# MCU.net
KiCad netlist of a schematic drawn in Altium Designer
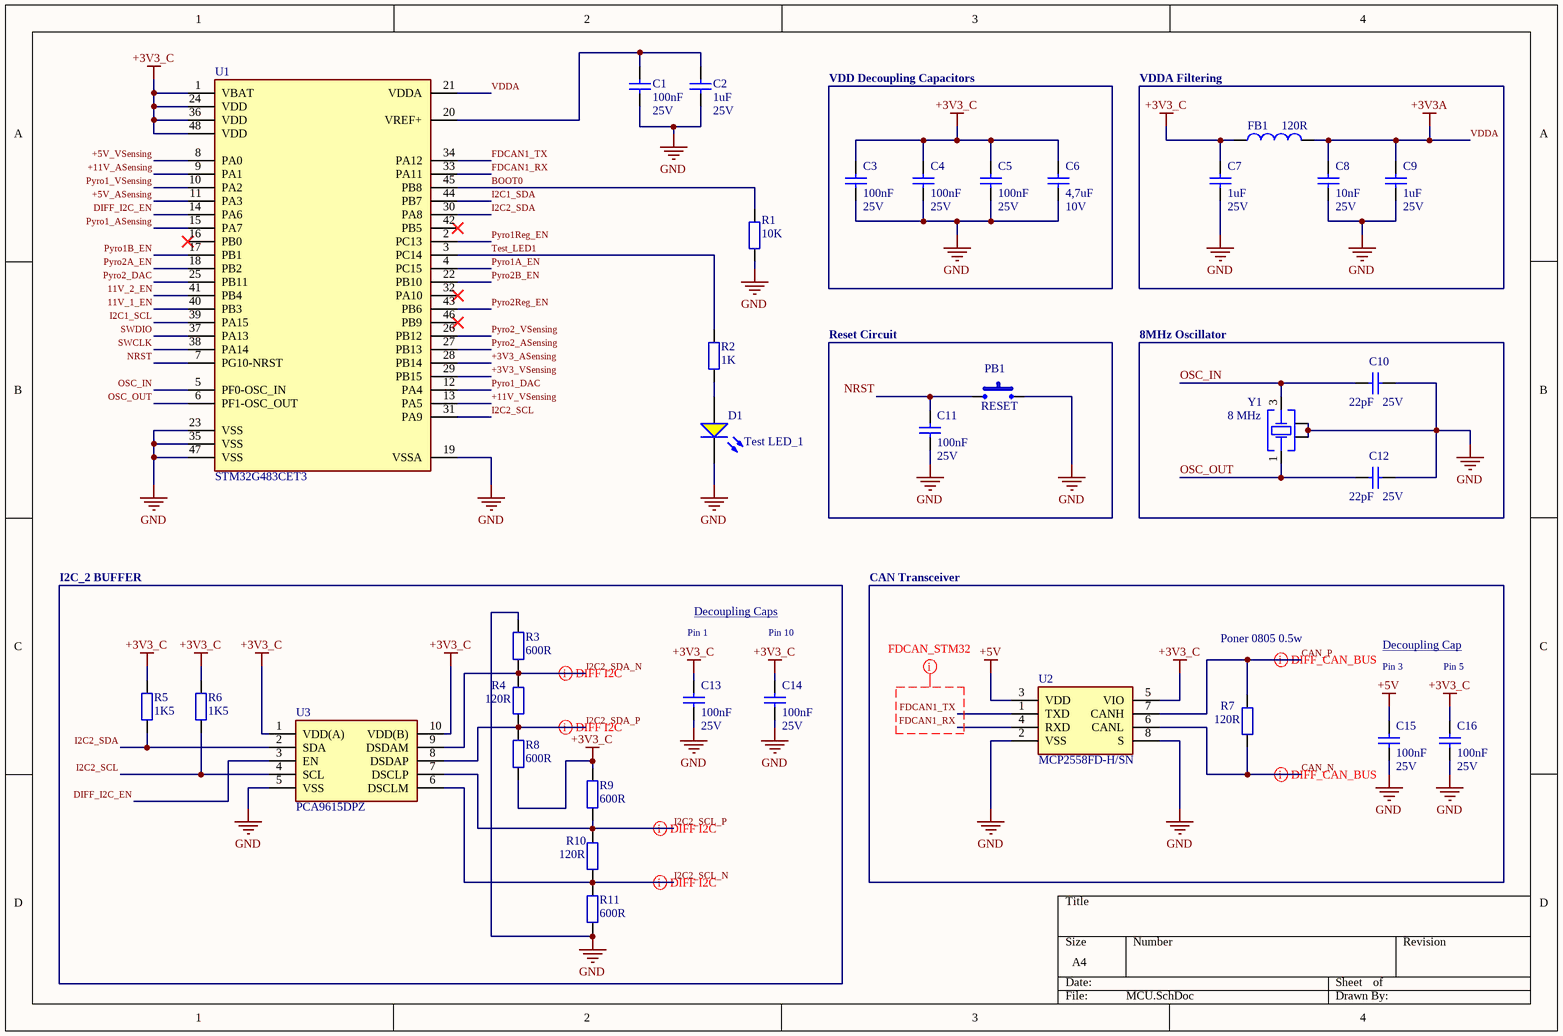
[diagram p0: MCU.SchDoc]

(export (version "E")
  (design (tool "Eeschema 10.0.6"))
  (components
    (comp (ref "C1")
      (value "100nF")
      (footprint "MY_0603")
      (description "Capacitor, 100nF, 0603, 25V")
      (fields
        (field (name "VOLTAGE") "25V")
        (field (name "MANUFACTURER") "Wurth Elektronik")
        (field (name "MANUFACTURER PART NUMBER") "885012206071")
      )
      (libsource (lib "LEEM UPM") (part "Cap ceramic"))
    )
    (comp (ref "C2")
      (value "1uF")
      (footprint "MY_0603")
      (description "Capacitor, 1uF, 0603, 25V")
      (fields
        (field (name "VOLTE") "25V")
        (field (name "MANUFACTURER") "Wurth Elektronik")
        (field (name "MANUFACTURER PART NUMBER") "885012206052")
      )
      (libsource (lib "LEEM UPM") (part "Cap ceramic"))
    )
    (comp (ref "C3")
      (value "100nF")
      (footprint "MY_0603")
      (description "Capacitor, 100nF, 0603, 25V")
      (fields
        (field (name "VOLTAGE") "25V")
        (field (name "MANUFACTURER") "Wurth Elektronik")
        (field (name "MANUFACTURER PART NUMBER") "885012206071")
      )
      (libsource (lib "LEEM UPM") (part "Cap ceramic"))
    )
    (comp (ref "C4")
      (value "100nF")
      (footprint "MY_0603")
      (description "Capacitor, 100nF, 0603, 25V")
      (fields
        (field (name "VOLTAGE") "25V")
        (field (name "MANUFACTURER") "Wurth Elektronik")
        (field (name "MANUFACTURER PART NUMBER") "885012206071")
      )
      (libsource (lib "LEEM UPM") (part "Cap ceramic"))
    )
    (comp (ref "C5")
      (value "100nF")
      (footprint "MY_0603")
      (description "Capacitor, 100nF, 0603, 25V")
      (fields
        (field (name "VOLTAGE") "25V")
        (field (name "MANUFACTURER") "Wurth Elektronik")
        (field (name "MANUFACTURER PART NUMBER") "885012206071")
      )
      (libsource (lib "LEEM UPM") (part "Cap ceramic"))
    )
    (comp (ref "C6")
      (value "4,7uF")
      (footprint "MY_0603")
      (description "Capacitor, 4.7uF, 0603, 25V")
      (fields
        (field (name "VOLTE") "10V")
        (field (name "MANUFACTURER") "Wurth Elektronik")
        (field (name "MANUFACTURER PART NUMBER") "885012106012")
      )
      (libsource (lib "LEEM UPM") (part "Cap ceramic"))
    )
    (comp (ref "C7")
      (value "1uF")
      (footprint "MY_0603")
      (description "Capacitor, 1uF, 0603, 25V")
      (fields
        (field (name "VOLTE") "25V")
        (field (name "MANUFACTURER") "Wurth Elektronik")
        (field (name "MANUFACTURER PART NUMBER") "885012206052")
      )
      (libsource (lib "LEEM UPM") (part "Cap ceramic"))
    )
    (comp (ref "C8")
      (value "25V")
      (footprint "MY_0603")
      (description "Capacitor, 10nF, 0603, 25V")
      (fields
        (field (name "ALTIUM_VALUE") "10nF")
        (field (name "MANUFACTURER") "Wurth Elektronik")
        (field (name "MANUFACTURER PART NUMBER") "885012206065")
      )
      (libsource (lib "LEEM UPM") (part "Cap ceramic"))
    )
    (comp (ref "C9")
      (value "1uF")
      (footprint "MY_0603")
      (description "Capacitor, 1uF, 0603, 25V")
      (fields
        (field (name "VOLTE") "25V")
        (field (name "MANUFACTURER") "Wurth Elektronik")
        (field (name "MANUFACTURER PART NUMBER") "885012206052")
      )
      (libsource (lib "LEEM UPM") (part "Cap ceramic"))
    )
    (comp (ref "C10")
      (value "22pF")
      (footprint "MY_0603")
      (description "Capacitor, 22pF, 0603, 25V")
      (fields
        (field (name "VOLTE") "25V")
        (field (name "MANUFACTURER") "Wurth Elektronik")
        (field (name "MANUFACTURER PART NUMBER") "885012006034")
      )
      (libsource (lib "LEEM UPM") (part "Cap ceramic"))
    )
    (comp (ref "C11")
      (value "100nF")
      (footprint "MY_0603")
      (description "Capacitor, 100nF, 0603, 25V")
      (fields
        (field (name "VOLTAGE") "25V")
        (field (name "MANUFACTURER") "Wurth Elektronik")
        (field (name "MANUFACTURER PART NUMBER") "885012206071")
      )
      (libsource (lib "LEEM UPM") (part "Cap ceramic"))
    )
    (comp (ref "C12")
      (value "22pF")
      (footprint "MY_0603")
      (description "Capacitor, 22pF, 0603, 25V")
      (fields
        (field (name "VOLTE") "25V")
        (field (name "MANUFACTURER") "Wurth Elektronik")
        (field (name "MANUFACTURER PART NUMBER") "885012006034")
      )
      (libsource (lib "LEEM UPM") (part "Cap ceramic"))
    )
    (comp (ref "C13")
      (value "100nF")
      (footprint "MY_0603")
      (description "Capacitor, 100nF, 0603, 25V")
      (fields
        (field (name "VOLTAGE") "25V")
        (field (name "MANUFACTURER") "Wurth Elektronik")
        (field (name "MANUFACTURER PART NUMBER") "885012206071")
      )
      (libsource (lib "LEEM UPM") (part "Cap ceramic"))
    )
    (comp (ref "C14")
      (value "100nF")
      (footprint "MY_0603")
      (description "Capacitor, 100nF, 0603, 25V")
      (fields
        (field (name "VOLTAGE") "25V")
        (field (name "MANUFACTURER") "Wurth Elektronik")
        (field (name "MANUFACTURER PART NUMBER") "885012206071")
      )
      (libsource (lib "LEEM UPM") (part "Cap ceramic"))
    )
    (comp (ref "C15")
      (value "100nF")
      (footprint "MY_0603")
      (description "Capacitor, 100nF, 0603, 25V")
      (fields
        (field (name "VOLTAGE") "25V")
        (field (name "MANUFACTURER") "Wurth Elektronik")
        (field (name "MANUFACTURER PART NUMBER") "885012206071")
      )
      (libsource (lib "LEEM UPM") (part "Cap ceramic"))
    )
    (comp (ref "C16")
      (value "100nF")
      (footprint "MY_0603")
      (description "Capacitor, 100nF, 0603, 25V")
      (fields
        (field (name "VOLTAGE") "25V")
        (field (name "MANUFACTURER") "Wurth Elektronik")
        (field (name "MANUFACTURER PART NUMBER") "885012206071")
      )
      (libsource (lib "LEEM UPM") (part "Cap ceramic"))
    )
    (comp (ref "D1")
      (value "Test LED_1")
      (footprint "WL-SMCW_0805_150080xx75000")
      (description "LED, 0805, Yellow")
      (fields
        (field (name "MANUFACTURER") "Wurth Elektronik")
        (field (name "MANUFACTURER PART NUMBER") "150080YS75000")
      )
      (libsource (lib "Altium Content Vault") (part "LED_Yellow_2A-1K"))
    )
    (comp (ref "FB1")
      (value "120R")
      (footprint "WE-CBF_0603_L1.6W0.8H0.8_HC")
      (description "Ferrite Bead, 120R at 100MHz, 0603, 2 A")
      (fields
        (field (name "MANUFACTURER") "Wurth Elektronik")
        (field (name "MANUFACTURER PART NUMBER") "742792625")
      )
      (libsource (lib "Altium Content Vault") (part "Ferrite"))
    )
    (comp (ref "PB1")
      (value "RESET")
      (footprint "Push Button-Footprint-1")
      (description "Push Button")
      (fields (field (name "SOURCE") "IFS_Altium.SchLib"))
      (libsource (lib "LEEM UPM") (part "Push Button"))
    )
    (comp (ref "R1")
      (value "10K")
      (footprint "R0603-0.45")
      (description "Resistor, 10K, 0603, 0.1W")
      (fields (field (name "MANUFACTURER") "Wurth") (field (name "MANUFACTURER PART NUMBER") "560112116005"))
      (libsource (lib "IFS_Altium") (part "R"))
    )
    (comp (ref "R2")
      (value "1K")
      (footprint "R0603-0.45")
      (description "Resistor, 1K, 0603, 0.1W")
      (fields (field (name "MANUFACTURER") "Wurth") (field (name "MANUFACTURER PART NUMBER") "560112116014"))
      (libsource (lib "LEEM UPM") (part "RK73H2ALTD1004F"))
    )
    (comp (ref "R3")
      (value "600R")
      (footprint "R0805-0.45")
      (description "Resistor, 600R, 0805, 0.5W")
      (fields
        (field (name "MANUFACTURER") "Panasonic")
        (field (name "MANUFACTURER PART NUMBER") "ERJ-6ENF6040V")
      )
      (libsource (lib "LEEM UPM") (part "RK73H2ALTD1004F"))
    )
    (comp (ref "R4")
      (value "120R")
      (footprint "R0805-0.45")
      (description "Resistor, 120R, 0805, 0.25W")
      (fields
        (field (name "MANUFACTURER") "Vishay")
        (field (name "MANUFACTURER PART NUMBER") "RCS0805120RFKEA")
      )
      (libsource (lib "LEEM UPM") (part "RK73H2ALTD1004F"))
    )
    (comp (ref "R5")
      (value "1K5")
      (footprint "R0603-0.45")
      (description "Resistor, 1.5K, 0603, 0.1W")
      (fields (field (name "MANUFACTURER") "Wurth") (field (name "MANUFACTURER PART NUMBER") "560112116038"))
      (libsource (lib "LEEM UPM") (part "RK73H2ALTD1004F"))
    )
    (comp (ref "R6")
      (value "1K5")
      (footprint "R0603-0.45")
      (description "Resistor, 1.5K, 0603, 0.1W")
      (fields (field (name "MANUFACTURER") "Wurth") (field (name "MANUFACTURER PART NUMBER") "560112116038"))
      (libsource (lib "LEEM UPM") (part "RK73H2ALTD1004F"))
    )
    (comp (ref "R7")
      (value "120R")
      (footprint "R0805-0.45")
      (description "Resistor, 120R, 0805, 0.25W")
      (fields
        (field (name "MANUFACTURER") "Vishay")
        (field (name "MANUFACTURER PART NUMBER") "RCS0805120RFKEA")
      )
      (libsource (lib "LEEM UPM") (part "RK73H2ALTD1004F"))
    )
    (comp (ref "R8")
      (value "600R")
      (footprint "R0805-0.45")
      (description "Resistor, 600R, 0805, 0.5W")
      (fields
        (field (name "MANUFACTURER") "Panasonic")
        (field (name "MANUFACTURER PART NUMBER") "ERJ-6ENF6040V")
      )
      (libsource (lib "LEEM UPM") (part "RK73H2ALTD1004F"))
    )
    (comp (ref "R9")
      (value "600R")
      (footprint "R0805-0.45")
      (description "Resistor, 600R, 0805, 0.5W")
      (fields
        (field (name "MANUFACTURER") "Panasonic")
        (field (name "MANUFACTURER PART NUMBER") "ERJ-6ENF6040V")
      )
      (libsource (lib "LEEM UPM") (part "RK73H2ALTD1004F"))
    )
    (comp (ref "R10")
      (value "120R")
      (footprint "R0805-0.45")
      (description "Resistor, 120R, 0805, 0.25W")
      (fields
        (field (name "MANUFACTURER") "Vishay")
        (field (name "MANUFACTURER PART NUMBER") "RCS0805120RFKEA")
      )
      (libsource (lib "LEEM UPM") (part "RK73H2ALTD1004F"))
    )
    (comp (ref "R11")
      (value "600R")
      (footprint "R0805-0.45")
      (description "Resistor, 600R, 0805, 0.5W")
      (fields
        (field (name "MANUFACTURER") "Panasonic")
        (field (name "MANUFACTURER PART NUMBER") "ERJ-6ENF6040V")
      )
      (libsource (lib "LEEM UPM") (part "RK73H2ALTD1004F"))
    )
    (comp (ref "U1")
      (value "STM32G483CET3")
      (footprint "STM32G0C1RET6-Footprint-1")
      (fields (field (name "MANUFACTURER") "STMicroelectronics"))
      (libsource (lib "LEEM UPM") (part "STM32G483xE"))
    )
    (comp (ref "U2")
      (value "MCP2558FD-H/SN")
      (footprint "MCP2557FD-H_SN-Footprint-1")
      (description "Interfaz CI CAN CAN FD Transceiver with Silent Mode")
      (fields (field (name "MANUFACTURER") "Microchip Technology"))
      (libsource (lib "LEEM UPM") (part "MCP2558FD-H_SN-Symbol-1"))
    )
    (comp (ref "U3")
      (value "PCA9615DPZ")
      (footprint "PCA9615DPZ-Footprint-1")
      (description "2 Channel  I2C-busbuffer")
      (fields (field (name "MANUFACTURER") "NXP Semiconductors"))
      (libsource (lib "LEEM UPM") (part "PCA9615DPZ-Symbol-1"))
    )
    (comp (ref "Y1")
      (value "8 MHz")
      (footprint "WE-XTAL_CFPX-104")
      (description "WE-XTAL Quartz Crystal, SMT, CFPX-104, 8MHz,")
      (fields
        (field (name "MANUFACTURER") "Wurth Elektronik")
        (field (name "MANUFACTURER PART NUMBER") "830055663")
      )
      (libsource (lib "LEEM UPM") (part "830108161901"))
    )
  )
  (nets
    (net (code "1") (name "+3V3A") (class "Default")
      (node (ref "C8") (pin "2") (pinfunction "2_2") (pintype "passive"))
      (node (ref "C9") (pin "2") (pinfunction "2_2") (pintype "passive"))
      (node (ref "FB1") (pin "2") (pinfunction "2_2") (pintype "passive"))
      (node (ref "U1") (pin "21") (pinfunction "VDDA_21") (pintype "passive"))
    )
    (net (code "2") (name "+3V3_C") (class "Default")
      (node (ref "C13") (pin "2") (pinfunction "2_2") (pintype "passive"))
      (node (ref "C14") (pin "2") (pinfunction "2_2") (pintype "passive"))
      (node (ref "C16") (pin "2") (pinfunction "2_2") (pintype "passive"))
      (node (ref "C3") (pin "2") (pinfunction "2_2") (pintype "passive"))
      (node (ref "C4") (pin "2") (pinfunction "2_2") (pintype "passive"))
      (node (ref "C5") (pin "2") (pinfunction "2_2") (pintype "passive"))
      (node (ref "C6") (pin "2") (pinfunction "2_2") (pintype "passive"))
      (node (ref "C7") (pin "2") (pinfunction "2_2") (pintype "passive"))
      (node (ref "FB1") (pin "1") (pinfunction "1_1") (pintype "passive"))
      (node (ref "R5") (pin "1") (pinfunction "1_1") (pintype "passive"))
      (node (ref "R6") (pin "1") (pinfunction "1_1") (pintype "passive"))
      (node (ref "R8") (pin "2") (pinfunction "2_2") (pintype "passive"))
      (node (ref "R9") (pin "1") (pinfunction "1_1") (pintype "passive"))
      (node (ref "U1") (pin "1") (pinfunction "VBAT_1") (pintype "passive"))
      (node (ref "U1") (pin "24") (pinfunction "VDD_24") (pintype "passive"))
      (node (ref "U1") (pin "36") (pinfunction "VDD_36") (pintype "passive"))
      (node (ref "U1") (pin "48") (pinfunction "VDD_48") (pintype "passive"))
      (node (ref "U2") (pin "5") (pinfunction "VIO_5") (pintype "passive"))
      (node (ref "U3") (pin "1") (pinfunction "VDD(A)_1") (pintype "passive"))
      (node (ref "U3") (pin "10") (pinfunction "VDD(B)_10") (pintype "passive"))
    )
    (net (code "3") (name "+5V") (class "Default")
      (node (ref "C15") (pin "2") (pinfunction "2_2") (pintype "passive"))
      (node (ref "U2") (pin "3") (pinfunction "VDD_3") (pintype "passive"))
    )
    (net (code "4") (name "/+3V3_ASensing") (class "Default")
      (node (ref "U1") (pin "28") (pinfunction "PB14_28") (pintype "passive"))
    )
    (net (code "5") (name "/+3V3_VSensing") (class "Default")
      (node (ref "U1") (pin "29") (pinfunction "PB15_29") (pintype "passive"))
    )
    (net (code "6") (name "/+5V_ASensing") (class "Default")
      (node (ref "U1") (pin "11") (pinfunction "PA3_11") (pintype "passive"))
    )
    (net (code "7") (name "/+5V_VSensing") (class "Default")
      (node (ref "U1") (pin "8") (pinfunction "PA0_8") (pintype "passive"))
    )
    (net (code "8") (name "/+11V_ASensing") (class "Default")
      (node (ref "U1") (pin "9") (pinfunction "PA1_9") (pintype "passive"))
    )
    (net (code "9") (name "/+11V_VSensing") (class "Default")
      (node (ref "U1") (pin "13") (pinfunction "PA5_13") (pintype "passive"))
    )
    (net (code "10") (name "/11V_1_EN") (class "Default")
      (node (ref "U1") (pin "40") (pinfunction "PB3_40") (pintype "passive"))
    )
    (net (code "11") (name "/11V_2_EN") (class "Default")
      (node (ref "U1") (pin "41") (pinfunction "PB4_41") (pintype "passive"))
    )
    (net (code "13") (name "/BOOT0") (class "Default")
      (node (ref "R1") (pin "1") (pinfunction "1_1") (pintype "passive"))
      (node (ref "U1") (pin "45") (pinfunction "PB8_45") (pintype "passive"))
    )
    (net (code "14") (name "/CAN_N") (class "Default")
      (node (ref "R7") (pin "1") (pinfunction "1_1") (pintype "passive"))
      (node (ref "U2") (pin "6") (pinfunction "CANL_6") (pintype "passive"))
    )
    (net (code "15") (name "/CAN_P") (class "Default")
      (node (ref "R7") (pin "2") (pinfunction "2_2") (pintype "passive"))
      (node (ref "U2") (pin "7") (pinfunction "CANH_7") (pintype "passive"))
    )
    (net (code "16") (name "/DIFF_I2C_EN") (class "Default")
      (node (ref "U1") (pin "14") (pinfunction "PA6_14") (pintype "passive"))
      (node (ref "U3") (pin "3") (pinfunction "EN_3") (pintype "passive"))
    )
    (net (code "17") (name "/FDCAN1_RX") (class "Default")
      (node (ref "U1") (pin "33") (pinfunction "PA11_33") (pintype "passive"))
      (node (ref "U2") (pin "4") (pinfunction "RXD_4") (pintype "passive"))
    )
    (net (code "18") (name "/FDCAN1_TX") (class "Default")
      (node (ref "U1") (pin "34") (pinfunction "PA12_34") (pintype "passive"))
      (node (ref "U2") (pin "1") (pinfunction "TXD_1") (pintype "passive"))
    )
    (net (code "19") (name "/I2C1_SCL") (class "Default")
      (node (ref "U1") (pin "39") (pinfunction "PA15_39") (pintype "passive"))
    )
    (net (code "20") (name "/I2C1_SDA") (class "Default")
      (node (ref "U1") (pin "44") (pinfunction "PB7_44") (pintype "passive"))
    )
    (net (code "21") (name "/I2C2_SCL") (class "Default")
      (node (ref "R6") (pin "2") (pinfunction "2_2") (pintype "passive"))
      (node (ref "U1") (pin "31") (pinfunction "PA9_31") (pintype "passive"))
      (node (ref "U3") (pin "4") (pinfunction "SCL_4") (pintype "passive"))
    )
    (net (code "22") (name "/I2C2_SCL_N") (class "Default")
      (node (ref "R10") (pin "1") (pinfunction "1_1") (pintype "passive"))
      (node (ref "R11") (pin "1") (pinfunction "1_1") (pintype "passive"))
      (node (ref "U3") (pin "6") (pinfunction "DSCLM_6") (pintype "passive"))
    )
    (net (code "23") (name "/I2C2_SCL_P") (class "Default")
      (node (ref "R10") (pin "2") (pinfunction "2_2") (pintype "passive"))
      (node (ref "R9") (pin "2") (pinfunction "2_2") (pintype "passive"))
      (node (ref "U3") (pin "7") (pinfunction "DSCLP_7") (pintype "passive"))
    )
    (net (code "24") (name "/I2C2_SDA") (class "Default")
      (node (ref "R5") (pin "2") (pinfunction "2_2") (pintype "passive"))
      (node (ref "U1") (pin "30") (pinfunction "PA8_30") (pintype "passive"))
      (node (ref "U3") (pin "2") (pinfunction "SDA_2") (pintype "passive"))
    )
    (net (code "25") (name "/I2C2_SDA_N") (class "Default")
      (node (ref "R3") (pin "2") (pinfunction "2_2") (pintype "passive"))
      (node (ref "R4") (pin "2") (pinfunction "2_2") (pintype "passive"))
      (node (ref "U3") (pin "9") (pinfunction "DSDAM_9") (pintype "passive"))
    )
    (net (code "26") (name "/I2C2_SDA_P") (class "Default")
      (node (ref "R4") (pin "1") (pinfunction "1_1") (pintype "passive"))
      (node (ref "R8") (pin "1") (pinfunction "1_1") (pintype "passive"))
      (node (ref "U3") (pin "8") (pinfunction "DSDAP_8") (pintype "passive"))
    )
    (net (code "27") (name "/NRST") (class "Default")
      (node (ref "C11") (pin "2") (pinfunction "2_2") (pintype "passive"))
      (node (ref "PB1") (pin "1") (pinfunction "1_1") (pintype "passive"))
      (node (ref "U1") (pin "7") (pinfunction "PG10-NRST_7") (pintype "passive"))
    )
    (net (code "28") (name "/OSC_IN") (class "Default")
      (node (ref "C10") (pin "1") (pinfunction "1_1") (pintype "passive"))
      (node (ref "U1") (pin "5") (pinfunction "PF0-OSC_IN_5") (pintype "passive"))
      (node (ref "Y1") (pin "3") (pinfunction "Crystal_3") (pintype "passive"))
    )
    (net (code "29") (name "/OSC_OUT") (class "Default")
      (node (ref "C12") (pin "1") (pinfunction "1_1") (pintype "passive"))
      (node (ref "U1") (pin "6") (pinfunction "PF1-OSC_OUT_6") (pintype "passive"))
      (node (ref "Y1") (pin "1") (pinfunction "Crystal_1") (pintype "passive"))
    )
    (net (code "30") (name "/Pyro1A_EN") (class "Default")
      (node (ref "U1") (pin "4") (pinfunction "PC15_4") (pintype "passive"))
    )
    (net (code "31") (name "/Pyro1B_EN") (class "Default")
      (node (ref "U1") (pin "17") (pinfunction "PB1_17") (pintype "passive"))
    )
    (net (code "32") (name "/Pyro1Reg_EN") (class "Default")
      (node (ref "U1") (pin "2") (pinfunction "PC13_2") (pintype "passive"))
    )
    (net (code "33") (name "/Pyro1_ASensing") (class "Default")
      (node (ref "U1") (pin "15") (pinfunction "PA7_15") (pintype "passive"))
    )
    (net (code "34") (name "/Pyro1_DAC") (class "Default")
      (node (ref "U1") (pin "12") (pinfunction "PA4_12") (pintype "passive"))
    )
    (net (code "35") (name "/Pyro1_VSensing") (class "Default")
      (node (ref "U1") (pin "10") (pinfunction "PA2_10") (pintype "passive"))
    )
    (net (code "36") (name "/Pyro2A_EN") (class "Default")
      (node (ref "U1") (pin "18") (pinfunction "PB2_18") (pintype "passive"))
    )
    (net (code "37") (name "/Pyro2B_EN") (class "Default")
      (node (ref "U1") (pin "22") (pinfunction "PB10_22") (pintype "passive"))
    )
    (net (code "38") (name "/Pyro2Reg_EN") (class "Default")
      (node (ref "U1") (pin "43") (pinfunction "PB6_43") (pintype "passive"))
    )
    (net (code "39") (name "/Pyro2_ASensing") (class "Default")
      (node (ref "U1") (pin "27") (pinfunction "PB13_27") (pintype "passive"))
    )
    (net (code "40") (name "/Pyro2_DAC") (class "Default")
      (node (ref "U1") (pin "25") (pinfunction "PB11_25") (pintype "passive"))
    )
    (net (code "41") (name "/Pyro2_VSensing") (class "Default")
      (node (ref "U1") (pin "26") (pinfunction "PB12_26") (pintype "passive"))
    )
    (net (code "42") (name "/SWCLK") (class "Default")
      (node (ref "U1") (pin "38") (pinfunction "PA14_38") (pintype "passive"))
    )
    (net (code "43") (name "/SWDIO") (class "Default")
      (node (ref "U1") (pin "37") (pinfunction "PA13_37") (pintype "passive"))
    )
    (net (code "44") (name "/Test_LED1") (class "Default")
      (node (ref "R2") (pin "2") (pinfunction "2_2") (pintype "passive"))
      (node (ref "U1") (pin "3") (pinfunction "PC14_3") (pintype "passive"))
    )
    (net (code "45") (name "GND") (class "Default")
      (node (ref "C1") (pin "1") (pinfunction "1_1") (pintype "passive"))
      (node (ref "C10") (pin "2") (pinfunction "2_2") (pintype "passive"))
      (node (ref "C11") (pin "1") (pinfunction "1_1") (pintype "passive"))
      (node (ref "C12") (pin "2") (pinfunction "2_2") (pintype "passive"))
      (node (ref "C13") (pin "1") (pinfunction "1_1") (pintype "passive"))
      (node (ref "C14") (pin "1") (pinfunction "1_1") (pintype "passive"))
      (node (ref "C15") (pin "1") (pinfunction "1_1") (pintype "passive"))
      (node (ref "C16") (pin "1") (pinfunction "1_1") (pintype "passive"))
      (node (ref "C2") (pin "1") (pinfunction "1_1") (pintype "passive"))
      (node (ref "C3") (pin "1") (pinfunction "1_1") (pintype "passive"))
      (node (ref "C4") (pin "1") (pinfunction "1_1") (pintype "passive"))
      (node (ref "C5") (pin "1") (pinfunction "1_1") (pintype "passive"))
      (node (ref "C6") (pin "1") (pinfunction "1_1") (pintype "passive"))
      (node (ref "C7") (pin "1") (pinfunction "1_1") (pintype "passive"))
      (node (ref "C8") (pin "1") (pinfunction "1_1") (pintype "passive"))
      (node (ref "C9") (pin "1") (pinfunction "1_1") (pintype "passive"))
      (node (ref "D1") (pin "1") (pinfunction "K_1") (pintype "passive"))
      (node (ref "PB1") (pin "2") (pinfunction "2_2") (pintype "passive"))
      (node (ref "R1") (pin "2") (pinfunction "2_2") (pintype "passive"))
      (node (ref "R11") (pin "2") (pinfunction "2_2") (pintype "passive"))
      (node (ref "R3") (pin "1") (pinfunction "1_1") (pintype "passive"))
      (node (ref "U1") (pin "19") (pinfunction "VSSA_19") (pintype "passive"))
      (node (ref "U1") (pin "23") (pinfunction "VSS_23") (pintype "passive"))
      (node (ref "U1") (pin "35") (pinfunction "VSS_35") (pintype "passive"))
      (node (ref "U1") (pin "47") (pinfunction "VSS_47") (pintype "passive"))
      (node (ref "U2") (pin "2") (pinfunction "VSS_2") (pintype "passive"))
      (node (ref "U2") (pin "8") (pinfunction "S_8") (pintype "passive"))
      (node (ref "U3") (pin "5") (pinfunction "VSS_5") (pintype "passive"))
      (node (ref "Y1") (pin "2") (pinfunction "GND_&_Lid_2") (pintype "passive"))
      (node (ref "Y1") (pin "4") (pinfunction "GND_&_Lid_4") (pintype "passive"))
    )
    (net (code "46") (name "Net-(D1-A)") (class "Default")
      (node (ref "D1") (pin "2") (pinfunction "A_2") (pintype "passive"))
      (node (ref "R2") (pin "1") (pinfunction "1_1") (pintype "passive"))
    )
    (net (code "47") (name "Net-(U1-VREF+)") (class "Default")
      (node (ref "C1") (pin "2") (pinfunction "2_2") (pintype "passive"))
      (node (ref "C2") (pin "2") (pinfunction "2_2") (pintype "passive"))
      (node (ref "U1") (pin "20") (pinfunction "VREF+_20") (pintype "passive"))
    )
    (net (code "48") (name "unconnected-(U1-PA10-Pad32)") (class "Default")
      (node (ref "U1") (pin "32") (pinfunction "PA10_32") (pintype "passive+no_connect"))
    )
    (net (code "49") (name "unconnected-(U1-PB0-Pad16)") (class "Default")
      (node (ref "U1") (pin "16") (pinfunction "PB0_16") (pintype "passive+no_connect"))
    )
    (net (code "50") (name "unconnected-(U1-PB5-Pad42)") (class "Default")
      (node (ref "U1") (pin "42") (pinfunction "PB5_42") (pintype "passive+no_connect"))
    )
    (net (code "51") (name "unconnected-(U1-PB9-Pad46)") (class "Default")
      (node (ref "U1") (pin "46") (pinfunction "PB9_46") (pintype "passive+no_connect"))
    )
  )
)
